# LionDrillCharger.net
KiCad netlist of a schematic drawn in EAGLE
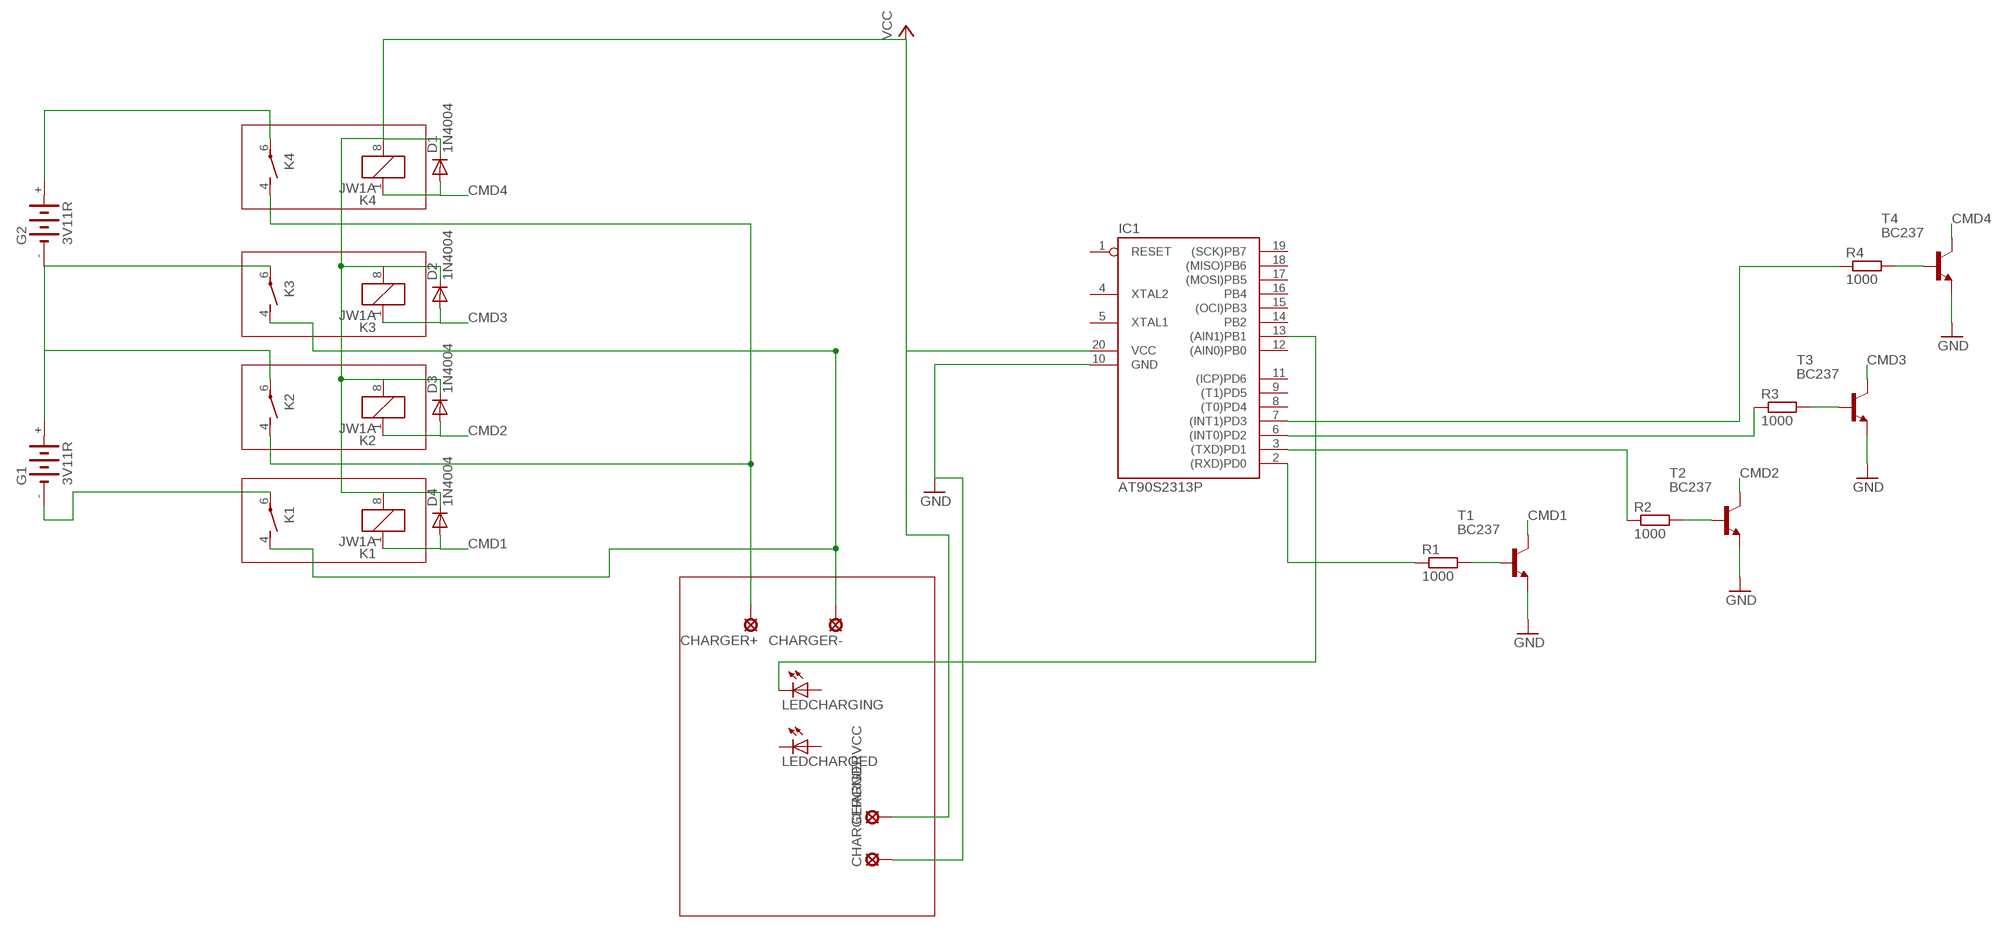
[diagram p0: schematic, sheet 1]

(export (version "E")
  (design (tool "Eeschema 10.0.6"))
  (components
    (comp (ref "CHARGER+")
      (value "LSP11")
      (footprint "eagle-import:LSP11")
      (libsource (lib "eagle-import") (part "LSP11"))
    )
    (comp (ref "CHARGER-")
      (value "LSP11")
      (footprint "eagle-import:LSP11")
      (libsource (lib "eagle-import") (part "LSP11"))
    )
    (comp (ref "CHARGERGND")
      (value "LSP11")
      (footprint "eagle-import:LSP11")
      (libsource (lib "eagle-import") (part "LSP11"))
    )
    (comp (ref "CHARGERVCC")
      (value "LSP11")
      (footprint "eagle-import:LSP11")
      (libsource (lib "eagle-import") (part "LSP11"))
    )
    (comp (ref "D1")
      (value "1N4004")
      (footprint "eagle-import:DO41-10")
      (libsource (lib "eagle-import") (part "1N4004"))
    )
    (comp (ref "D2")
      (value "1N4004")
      (footprint "eagle-import:DO41-10")
      (libsource (lib "eagle-import") (part "1N4004"))
    )
    (comp (ref "D3")
      (value "1N4004")
      (footprint "eagle-import:DO41-10")
      (libsource (lib "eagle-import") (part "1N4004"))
    )
    (comp (ref "D4")
      (value "1N4004")
      (footprint "eagle-import:DO41-10")
      (libsource (lib "eagle-import") (part "1N4004"))
    )
    (comp (ref "G1")
      (value "3V11R")
      (footprint "eagle-import:3V11R")
      (libsource (lib "eagle-import") (part "3V11R"))
    )
    (comp (ref "G2")
      (value "3V11R")
      (footprint "eagle-import:3V11R")
      (libsource (lib "eagle-import") (part "3V11R"))
    )
    (comp (ref "IC1")
      (value "AT90S2313P")
      (footprint "eagle-import:DIL20")
      (libsource (lib "eagle-import") (part "AT90S2313P"))
    )
    (comp (ref "K1")
      (value "JW1A")
      (footprint "eagle-import:JW1A")
      (libsource (lib "eagle-import") (part "JW1A"))
    )
    (comp (ref "K2")
      (value "JW1A")
      (footprint "eagle-import:JW1A")
      (libsource (lib "eagle-import") (part "JW1A"))
    )
    (comp (ref "K3")
      (value "JW1A")
      (footprint "eagle-import:JW1A")
      (libsource (lib "eagle-import") (part "JW1A"))
    )
    (comp (ref "K4")
      (value "JW1A")
      (footprint "eagle-import:JW1A")
      (libsource (lib "eagle-import") (part "JW1A"))
    )
    (comp (ref "LEDCHARGED")
      (value "LED3MM")
      (footprint "eagle-import:LED3MM")
      (libsource (lib "eagle-import") (part "LED3MM"))
    )
    (comp (ref "LEDCHARGING")
      (value "LED3MM")
      (footprint "eagle-import:LED3MM")
      (libsource (lib "eagle-import") (part "LED3MM"))
    )
    (comp (ref "R1")
      (value "1000")
      (footprint "eagle-import:0204_5")
      (libsource (lib "eagle-import") (part "R-EU_0204/5"))
    )
    (comp (ref "R2")
      (value "1000")
      (footprint "eagle-import:0204_5")
      (libsource (lib "eagle-import") (part "R-EU_0204/5"))
    )
    (comp (ref "R3")
      (value "1000")
      (footprint "eagle-import:0204_5")
      (libsource (lib "eagle-import") (part "R-EU_0204/5"))
    )
    (comp (ref "R4")
      (value "1000")
      (footprint "eagle-import:0204_5")
      (libsource (lib "eagle-import") (part "R-EU_0204/5"))
    )
    (comp (ref "T1")
      (value "BC237")
      (footprint "eagle-import:TO92")
      (libsource (lib "eagle-import") (part "BC237"))
    )
    (comp (ref "T2")
      (value "BC237")
      (footprint "eagle-import:TO92")
      (libsource (lib "eagle-import") (part "BC237"))
    )
    (comp (ref "T3")
      (value "BC237")
      (footprint "eagle-import:TO92")
      (libsource (lib "eagle-import") (part "BC237"))
    )
    (comp (ref "T4")
      (value "BC237")
      (footprint "eagle-import:TO92")
      (libsource (lib "eagle-import") (part "BC237"))
    )
  )
  (nets
    (net (code "1") (name "/CMD1") (class "Default")
      (node (ref "D4") (pin "A") (pinfunction "A_A") (pintype "passive"))
      (node (ref "K1") (pin "1") (pinfunction "1_1") (pintype "passive"))
      (node (ref "T1") (pin "3") (pinfunction "C_3") (pintype "passive"))
    )
    (net (code "2") (name "/CMD2") (class "Default")
      (node (ref "D3") (pin "A") (pinfunction "A_A") (pintype "passive"))
      (node (ref "K2") (pin "1") (pinfunction "1_1") (pintype "passive"))
      (node (ref "T2") (pin "3") (pinfunction "C_3") (pintype "passive"))
    )
    (net (code "3") (name "/CMD3") (class "Default")
      (node (ref "D2") (pin "A") (pinfunction "A_A") (pintype "passive"))
      (node (ref "K3") (pin "1") (pinfunction "1_1") (pintype "passive"))
      (node (ref "T3") (pin "3") (pinfunction "C_3") (pintype "passive"))
    )
    (net (code "4") (name "/CMD4") (class "Default")
      (node (ref "D1") (pin "A") (pinfunction "A_A") (pintype "passive"))
      (node (ref "K4") (pin "1") (pinfunction "1_1") (pintype "passive"))
      (node (ref "T4") (pin "3") (pinfunction "C_3") (pintype "passive"))
    )
    (net (code "5") (name "GND") (class "Default")
      (node (ref "CHARGERGND") (pin "MP") (pinfunction "MP_MP") (pintype "passive"))
      (node (ref "IC1") (pin "10") (pinfunction "GND_10") (pintype "power_in"))
      (node (ref "T1") (pin "1") (pinfunction "E_1") (pintype "passive"))
      (node (ref "T2") (pin "1") (pinfunction "E_1") (pintype "passive"))
      (node (ref "T3") (pin "1") (pinfunction "E_1") (pintype "passive"))
      (node (ref "T4") (pin "1") (pinfunction "E_1") (pintype "passive"))
    )
    (net (code "6") (name "Net-(IC1-(AIN1)PB1)") (class "Default")
      (node (ref "IC1") (pin "13") (pinfunction "(AIN1)PB1_13") (pintype "bidirectional"))
      (node (ref "LEDCHARGING") (pin "K") (pinfunction "C_K") (pintype "passive"))
    )
    (net (code "7") (name "Net-(IC1-(INT0)PD2)") (class "Default")
      (node (ref "IC1") (pin "6") (pinfunction "(INT0)PD2_6") (pintype "bidirectional"))
      (node (ref "R3") (pin "1") (pinfunction "1_1") (pintype "passive"))
    )
    (net (code "8") (name "Net-(IC1-(INT1)PD3)") (class "Default")
      (node (ref "IC1") (pin "7") (pinfunction "(INT1)PD3_7") (pintype "bidirectional"))
      (node (ref "R4") (pin "1") (pinfunction "1_1") (pintype "passive"))
    )
    (net (code "9") (name "Net-(IC1-(RXD)PD0)") (class "Default")
      (node (ref "IC1") (pin "2") (pinfunction "(RXD)PD0_2") (pintype "bidirectional"))
      (node (ref "R1") (pin "1") (pinfunction "1_1") (pintype "passive"))
    )
    (net (code "10") (name "Net-(IC1-(TXD)PD1)") (class "Default")
      (node (ref "IC1") (pin "3") (pinfunction "(TXD)PD1_3") (pintype "bidirectional"))
      (node (ref "R2") (pin "1") (pinfunction "1_1") (pintype "passive"))
    )
    (net (code "11") (name "Net-(K1A-P)") (class "Default")
      (node (ref "G1") (pin "-") (pinfunction "-_-") (pintype "passive"))
      (node (ref "K1") (pin "6") (pinfunction "P_6") (pintype "passive"))
    )
    (net (code "12") (name "Net-(K1A-S)") (class "Default")
      (node (ref "CHARGER-") (pin "MP") (pinfunction "MP_MP") (pintype "passive"))
      (node (ref "K1") (pin "4") (pinfunction "S_4") (pintype "passive"))
      (node (ref "K3") (pin "4") (pinfunction "S_4") (pintype "passive"))
    )
    (net (code "13") (name "Net-(K2A-P)") (class "Default")
      (node (ref "G1") (pin "+") (pinfunction "+_+") (pintype "passive"))
      (node (ref "G2") (pin "-") (pinfunction "-_-") (pintype "passive"))
      (node (ref "K2") (pin "6") (pinfunction "P_6") (pintype "passive"))
      (node (ref "K3") (pin "6") (pinfunction "P_6") (pintype "passive"))
    )
    (net (code "14") (name "Net-(K2A-S)") (class "Default")
      (node (ref "CHARGER+") (pin "MP") (pinfunction "MP_MP") (pintype "passive"))
      (node (ref "K2") (pin "4") (pinfunction "S_4") (pintype "passive"))
      (node (ref "K4") (pin "4") (pinfunction "S_4") (pintype "passive"))
    )
    (net (code "15") (name "Net-(K4A-P)") (class "Default")
      (node (ref "G2") (pin "+") (pinfunction "+_+") (pintype "passive"))
      (node (ref "K4") (pin "6") (pinfunction "P_6") (pintype "passive"))
    )
    (net (code "16") (name "Net-(T1-B)") (class "Default")
      (node (ref "R1") (pin "2") (pinfunction "2_2") (pintype "passive"))
      (node (ref "T1") (pin "2") (pinfunction "B_2") (pintype "passive"))
    )
    (net (code "17") (name "Net-(T2-B)") (class "Default")
      (node (ref "R2") (pin "2") (pinfunction "2_2") (pintype "passive"))
      (node (ref "T2") (pin "2") (pinfunction "B_2") (pintype "passive"))
    )
    (net (code "18") (name "Net-(T3-B)") (class "Default")
      (node (ref "R3") (pin "2") (pinfunction "2_2") (pintype "passive"))
      (node (ref "T3") (pin "2") (pinfunction "B_2") (pintype "passive"))
    )
    (net (code "19") (name "Net-(T4-B)") (class "Default")
      (node (ref "R4") (pin "2") (pinfunction "2_2") (pintype "passive"))
      (node (ref "T4") (pin "2") (pinfunction "B_2") (pintype "passive"))
    )
    (net (code "20") (name "VCC") (class "Default")
      (node (ref "CHARGERVCC") (pin "MP") (pinfunction "MP_MP") (pintype "passive"))
      (node (ref "D1") (pin "C") (pinfunction "C_C") (pintype "passive"))
      (node (ref "D2") (pin "C") (pinfunction "C_C") (pintype "passive"))
      (node (ref "D3") (pin "C") (pinfunction "C_C") (pintype "passive"))
      (node (ref "D4") (pin "C") (pinfunction "C_C") (pintype "passive"))
      (node (ref "IC1") (pin "20") (pinfunction "VCC_20") (pintype "power_in"))
      (node (ref "K1") (pin "8") (pinfunction "2_8") (pintype "passive"))
      (node (ref "K2") (pin "8") (pinfunction "2_8") (pintype "passive"))
      (node (ref "K3") (pin "8") (pinfunction "2_8") (pintype "passive"))
      (node (ref "K4") (pin "8") (pinfunction "2_8") (pintype "passive"))
    )
    (net (code "21") (name "unconnected-(IC1-(AIN0)PB0-Pad12)") (class "Default")
      (node (ref "IC1") (pin "12") (pinfunction "(AIN0)PB0_12") (pintype "bidirectional"))
    )
    (net (code "22") (name "unconnected-(IC1-(ICP)PD6-Pad11)") (class "Default")
      (node (ref "IC1") (pin "11") (pinfunction "(ICP)PD6_11") (pintype "bidirectional"))
    )
    (net (code "23") (name "unconnected-(IC1-(MISO)PB6-Pad18)") (class "Default")
      (node (ref "IC1") (pin "18") (pinfunction "(MISO)PB6_18") (pintype "bidirectional"))
    )
    (net (code "24") (name "unconnected-(IC1-(MOSI)PB5-Pad17)") (class "Default")
      (node (ref "IC1") (pin "17") (pinfunction "(MOSI)PB5_17") (pintype "bidirectional"))
    )
    (net (code "25") (name "unconnected-(IC1-(OCI)PB3-Pad15)") (class "Default")
      (node (ref "IC1") (pin "15") (pinfunction "(OCI)PB3_15") (pintype "bidirectional"))
    )
    (net (code "26") (name "unconnected-(IC1-(SCK)PB7-Pad19)") (class "Default")
      (node (ref "IC1") (pin "19") (pinfunction "(SCK)PB7_19") (pintype "bidirectional"))
    )
    (net (code "27") (name "unconnected-(IC1-(T0)PD4-Pad8)") (class "Default")
      (node (ref "IC1") (pin "8") (pinfunction "(T0)PD4_8") (pintype "bidirectional"))
    )
    (net (code "28") (name "unconnected-(IC1-(T1)PD5-Pad9)") (class "Default")
      (node (ref "IC1") (pin "9") (pinfunction "(T1)PD5_9") (pintype "bidirectional"))
    )
    (net (code "29") (name "unconnected-(IC1-PB2-Pad14)") (class "Default")
      (node (ref "IC1") (pin "14") (pinfunction "PB2_14") (pintype "bidirectional"))
    )
    (net (code "30") (name "unconnected-(IC1-PB4-Pad16)") (class "Default")
      (node (ref "IC1") (pin "16") (pinfunction "PB4_16") (pintype "bidirectional"))
    )
    (net (code "31") (name "unconnected-(IC1-RESET-Pad1)") (class "Default")
      (node (ref "IC1") (pin "1") (pinfunction "RESET_1") (pintype "bidirectional"))
    )
    (net (code "32") (name "unconnected-(IC1-XTAL1-Pad5)") (class "Default")
      (node (ref "IC1") (pin "5") (pinfunction "XTAL1_5") (pintype "bidirectional"))
    )
    (net (code "33") (name "unconnected-(IC1-XTAL2-Pad4)") (class "Default")
      (node (ref "IC1") (pin "4") (pinfunction "XTAL2_4") (pintype "bidirectional"))
    )
    (net (code "34") (name "unconnected-(LEDCHARGED-C-PadK)") (class "Default")
      (node (ref "LEDCHARGED") (pin "K") (pinfunction "C_K") (pintype "passive"))
    )
    (net (code "35") (name "unconnected-(LEDCHARGED-PadA)") (class "Default")
      (node (ref "LEDCHARGED") (pin "A") (pinfunction "A_A") (pintype "passive"))
    )
    (net (code "36") (name "unconnected-(LEDCHARGING-PadA)") (class "Default")
      (node (ref "LEDCHARGING") (pin "A") (pinfunction "A_A") (pintype "passive"))
    )
  )
)
